# OptronV7_PCB.net
KiCad netlist of a schematic drawn in EAGLE
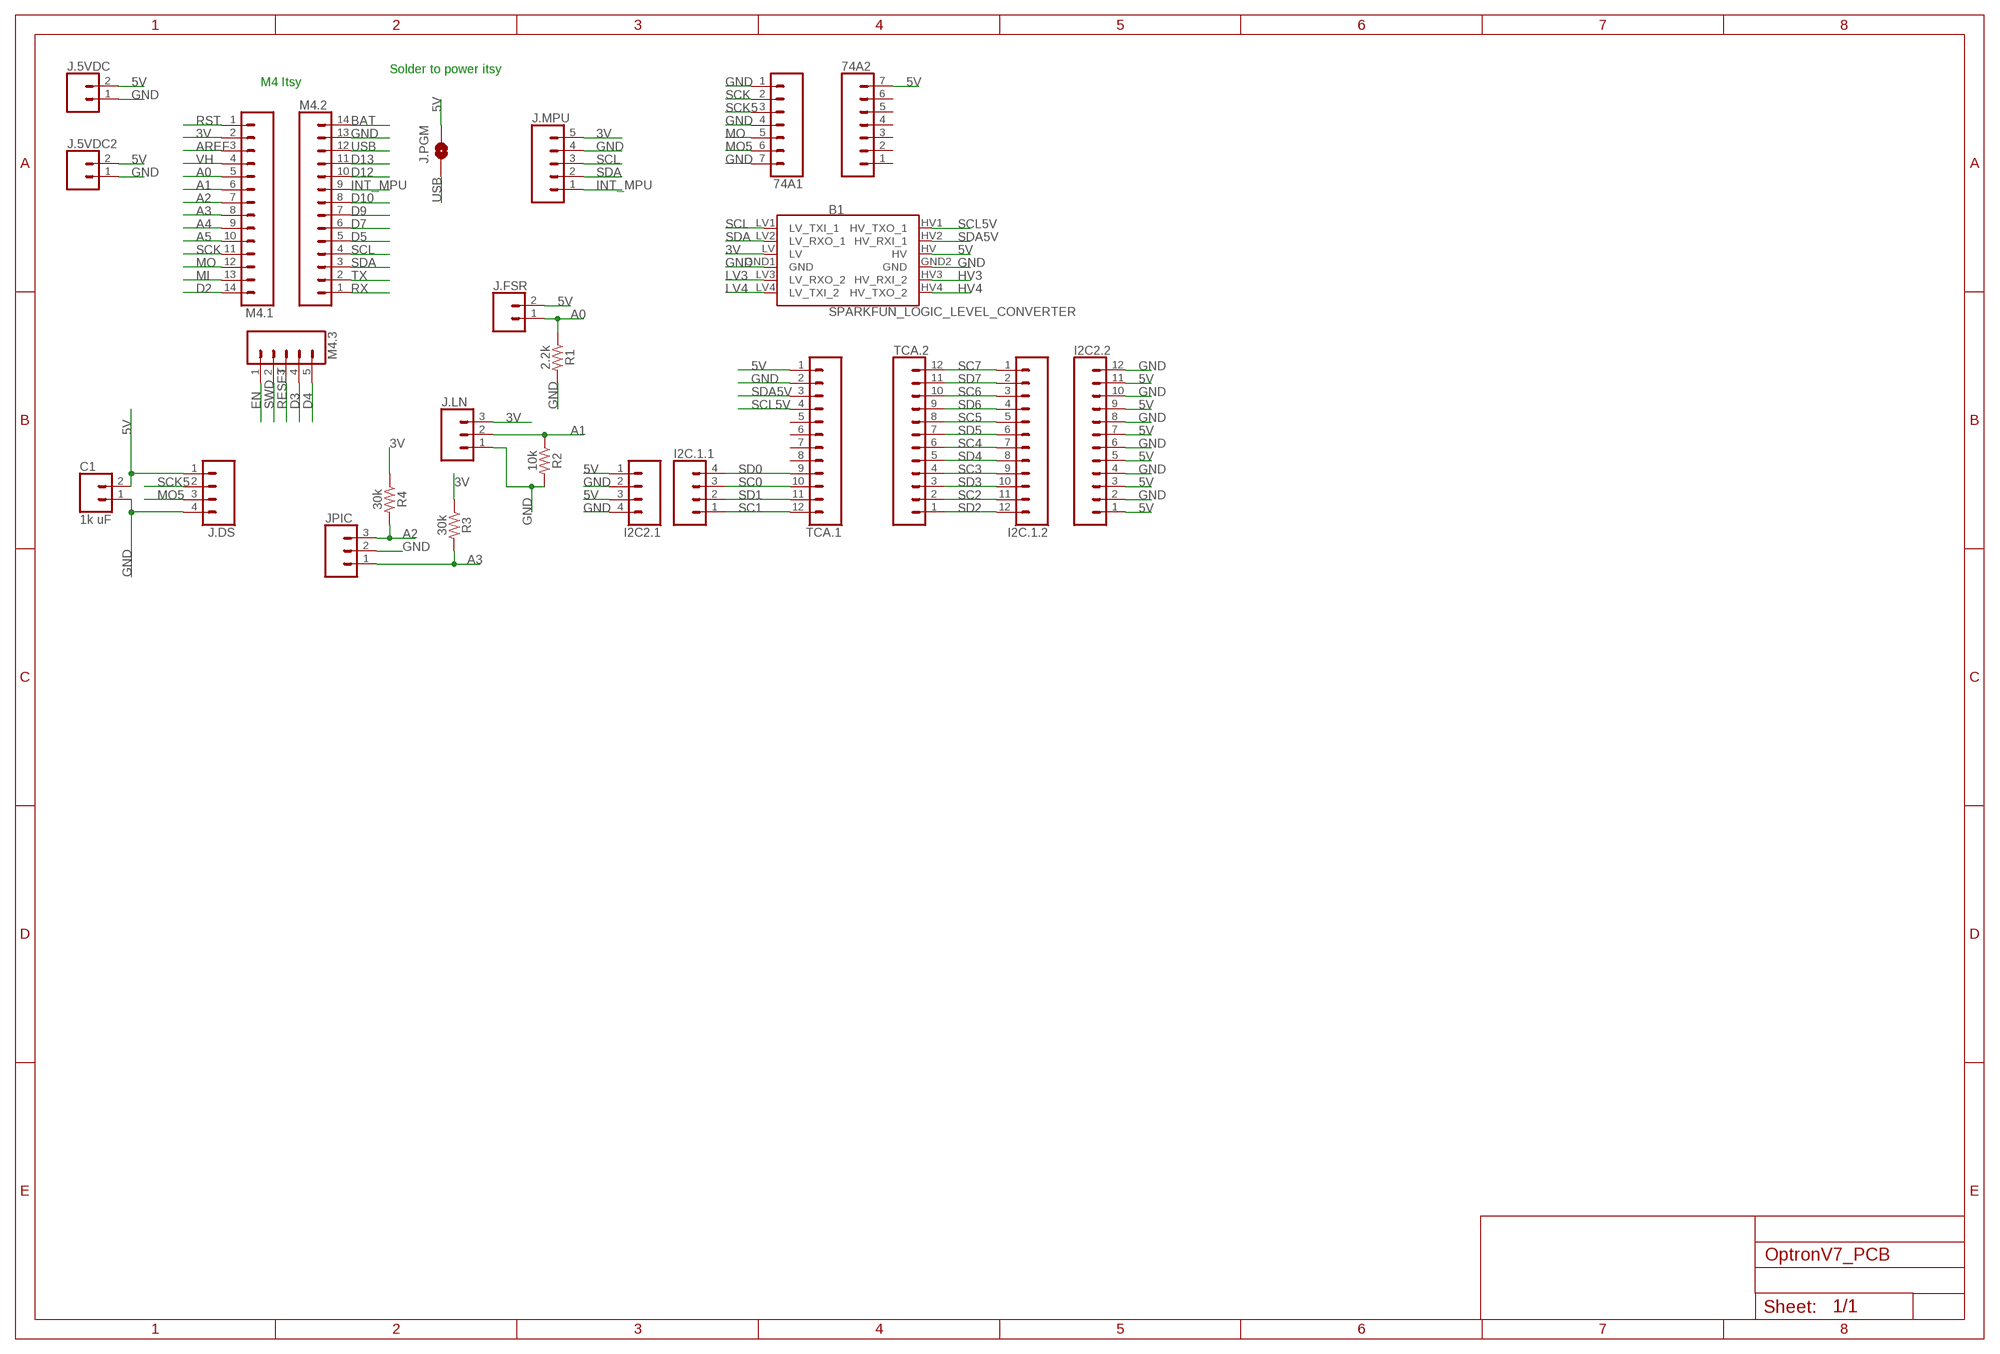
[diagram p0: schematic, sheet 1]

(export (version "E")
  (design (tool "Eeschema 10.0.6"))
  (components
    (comp (ref "74A1")
      (value "CONN_07")
      (footprint "eagle-import:1X07")
      (libsource (lib "eagle-import") (part "CONN_07"))
    )
    (comp (ref "74A2")
      (value "CONN_07")
      (footprint "eagle-import:1X07")
      (libsource (lib "eagle-import") (part "CONN_07"))
    )
    (comp (ref "B1")
      (value "SPARKFUN_LOGIC_LEVEL_CONVERTER")
      (footprint "eagle-import:SPARKFUN_LOGIC_LEVEL_CONVERTER")
      (libsource (lib "eagle-import") (part "SPARKFUN_LOGIC_LEVEL_CONVERTER"))
    )
    (comp (ref "C1")
      (value "1k uF")
      (footprint "eagle-import:1X02")
      (libsource (lib "eagle-import") (part "CONN_02"))
    )
    (comp (ref "I2C.1.1")
      (value "CONN_04")
      (footprint "eagle-import:1X04")
      (libsource (lib "eagle-import") (part "CONN_04"))
    )
    (comp (ref "I2C.1.2")
      (value "CONN_12")
      (footprint "eagle-import:1X12")
      (libsource (lib "eagle-import") (part "CONN_12"))
    )
    (comp (ref "I2C2.1")
      (value "CONN_04")
      (footprint "eagle-import:1X04")
      (libsource (lib "eagle-import") (part "CONN_04"))
    )
    (comp (ref "I2C2.2")
      (value "CONN_12")
      (footprint "eagle-import:1X12")
      (libsource (lib "eagle-import") (part "CONN_12"))
    )
    (comp (ref "J.5VDC")
      (value "CONN_02")
      (footprint "eagle-import:1X02")
      (libsource (lib "eagle-import") (part "CONN_02"))
    )
    (comp (ref "J.5VDC2")
      (value "CONN_02")
      (footprint "eagle-import:1X02")
      (libsource (lib "eagle-import") (part "CONN_02"))
    )
    (comp (ref "J.DS")
      (value "CONN_04")
      (footprint "eagle-import:1X04")
      (libsource (lib "eagle-import") (part "CONN_04"))
    )
    (comp (ref "J.FSR")
      (value "CONN_02")
      (footprint "eagle-import:1X02")
      (libsource (lib "eagle-import") (part "CONN_02"))
    )
    (comp (ref "J.LN")
      (value "CONN_03")
      (footprint "eagle-import:1X03")
      (libsource (lib "eagle-import") (part "CONN_03"))
    )
    (comp (ref "J.MPU")
      (value "CONN_05")
      (footprint "eagle-import:1X05")
      (libsource (lib "eagle-import") (part "CONN_05"))
    )
    (comp (ref "J.PGM")
      (value "JUMPER-SMT_2_NO_NO-SILK")
      (footprint "eagle-import:SMT-JUMPER_2_NO_NO-SILK")
      (libsource (lib "eagle-import") (part "JUMPER-SMT_2_NO_NO-SILK"))
    )
    (comp (ref "JPIC")
      (value "CONN_03")
      (footprint "eagle-import:1X03")
      (libsource (lib "eagle-import") (part "CONN_03"))
    )
    (comp (ref "M4.1")
      (value "CONN_14")
      (footprint "eagle-import:1X14")
      (libsource (lib "eagle-import") (part "CONN_14"))
    )
    (comp (ref "M4.2")
      (value "CONN_14")
      (footprint "eagle-import:1X14")
      (libsource (lib "eagle-import") (part "CONN_14"))
    )
    (comp (ref "M4.3")
      (value "CONN_05")
      (footprint "eagle-import:1X05")
      (libsource (lib "eagle-import") (part "CONN_05"))
    )
    (comp (ref "R1")
      (value "2.2k")
      (footprint "eagle-import:AXIAL-0.3")
      (libsource (lib "eagle-import") (part "10KOHM-HORIZ-1/4W-5%"))
    )
    (comp (ref "R2")
      (value "10k")
      (footprint "eagle-import:AXIAL-0.3")
      (libsource (lib "eagle-import") (part "10KOHM-HORIZ-1/4W-5%"))
    )
    (comp (ref "R3")
      (value "30k")
      (footprint "eagle-import:AXIAL-0.3")
      (libsource (lib "eagle-import") (part "10KOHM-HORIZ-1/4W-5%"))
    )
    (comp (ref "R4")
      (value "30k")
      (footprint "eagle-import:AXIAL-0.3")
      (libsource (lib "eagle-import") (part "10KOHM-HORIZ-1/4W-5%"))
    )
    (comp (ref "TCA.1")
      (value "CONN_12")
      (footprint "eagle-import:1X12")
      (libsource (lib "eagle-import") (part "CONN_12"))
    )
    (comp (ref "TCA.2")
      (value "CONN_12")
      (footprint "eagle-import:1X12")
      (libsource (lib "eagle-import") (part "CONN_12"))
    )
  )
  (nets
    (net (code "1") (name "/3V") (class "Default")
      (node (ref "B1") (pin "LV") (pinfunction "LV_LV") (pintype "power_in"))
      (node (ref "J.LN") (pin "3") (pinfunction "3_3") (pintype "passive"))
      (node (ref "J.MPU") (pin "5") (pinfunction "5_5") (pintype "passive"))
      (node (ref "M4.1") (pin "2") (pinfunction "2_2") (pintype "passive"))
      (node (ref "R3") (pin "P$1") (pinfunction "1_P$1") (pintype "passive"))
      (node (ref "R4") (pin "P$1") (pinfunction "1_P$1") (pintype "passive"))
    )
    (net (code "2") (name "/5V") (class "Default")
      (node (ref "74A2") (pin "7") (pinfunction "7_7") (pintype "passive"))
      (node (ref "B1") (pin "HV") (pinfunction "HV_HV") (pintype "power_in"))
      (node (ref "C1") (pin "2") (pinfunction "2_2") (pintype "passive"))
      (node (ref "I2C2.1") (pin "1") (pinfunction "1_1") (pintype "passive"))
      (node (ref "I2C2.1") (pin "3") (pinfunction "3_3") (pintype "passive"))
      (node (ref "I2C2.2") (pin "1") (pinfunction "1_1") (pintype "passive"))
      (node (ref "I2C2.2") (pin "11") (pinfunction "11_11") (pintype "passive"))
      (node (ref "I2C2.2") (pin "3") (pinfunction "3_3") (pintype "passive"))
      (node (ref "I2C2.2") (pin "5") (pinfunction "5_5") (pintype "passive"))
      (node (ref "I2C2.2") (pin "7") (pinfunction "7_7") (pintype "passive"))
      (node (ref "I2C2.2") (pin "9") (pinfunction "9_9") (pintype "passive"))
      (node (ref "J.5VDC") (pin "2") (pinfunction "2_2") (pintype "passive"))
      (node (ref "J.5VDC2") (pin "2") (pinfunction "2_2") (pintype "passive"))
      (node (ref "J.DS") (pin "1") (pinfunction "1_1") (pintype "passive"))
      (node (ref "J.FSR") (pin "2") (pinfunction "2_2") (pintype "passive"))
      (node (ref "J.PGM") (pin "2") (pinfunction "2_2") (pintype "passive"))
      (node (ref "TCA.1") (pin "1") (pinfunction "1_1") (pintype "passive"))
    )
    (net (code "3") (name "/A0") (class "Default")
      (node (ref "J.FSR") (pin "1") (pinfunction "1_1") (pintype "passive"))
      (node (ref "M4.1") (pin "5") (pinfunction "5_5") (pintype "passive"))
      (node (ref "R1") (pin "P$1") (pinfunction "1_P$1") (pintype "passive"))
    )
    (net (code "4") (name "/A1") (class "Default")
      (node (ref "J.LN") (pin "2") (pinfunction "2_2") (pintype "passive"))
      (node (ref "M4.1") (pin "6") (pinfunction "6_6") (pintype "passive"))
      (node (ref "R2") (pin "P$1") (pinfunction "1_P$1") (pintype "passive"))
    )
    (net (code "5") (name "/A2") (class "Default")
      (node (ref "JPIC") (pin "3") (pinfunction "3_3") (pintype "passive"))
      (node (ref "M4.1") (pin "7") (pinfunction "7_7") (pintype "passive"))
      (node (ref "R4") (pin "P$2") (pinfunction "2_P$2") (pintype "passive"))
    )
    (net (code "6") (name "/A3") (class "Default")
      (node (ref "JPIC") (pin "1") (pinfunction "1_1") (pintype "passive"))
      (node (ref "M4.1") (pin "8") (pinfunction "8_8") (pintype "passive"))
      (node (ref "R3") (pin "P$2") (pinfunction "2_P$2") (pintype "passive"))
    )
    (net (code "7") (name "/A4") (class "Default")
      (node (ref "M4.1") (pin "9") (pinfunction "9_9") (pintype "passive"))
    )
    (net (code "8") (name "/A5") (class "Default")
      (node (ref "M4.1") (pin "10") (pinfunction "10_10") (pintype "passive"))
    )
    (net (code "9") (name "/AREF") (class "Default")
      (node (ref "M4.1") (pin "3") (pinfunction "3_3") (pintype "passive"))
    )
    (net (code "10") (name "/BAT") (class "Default")
      (node (ref "M4.2") (pin "14") (pinfunction "14_14") (pintype "passive"))
    )
    (net (code "11") (name "/D2") (class "Default")
      (node (ref "M4.1") (pin "14") (pinfunction "14_14") (pintype "passive"))
    )
    (net (code "12") (name "/D3") (class "Default")
      (node (ref "M4.3") (pin "4") (pinfunction "4_4") (pintype "passive"))
    )
    (net (code "13") (name "/D4") (class "Default")
      (node (ref "M4.3") (pin "5") (pinfunction "5_5") (pintype "passive"))
    )
    (net (code "14") (name "/D5") (class "Default")
      (node (ref "M4.2") (pin "5") (pinfunction "5_5") (pintype "passive"))
    )
    (net (code "15") (name "/D7") (class "Default")
      (node (ref "M4.2") (pin "6") (pinfunction "6_6") (pintype "passive"))
    )
    (net (code "16") (name "/D9") (class "Default")
      (node (ref "M4.2") (pin "7") (pinfunction "7_7") (pintype "passive"))
    )
    (net (code "17") (name "/D10") (class "Default")
      (node (ref "M4.2") (pin "8") (pinfunction "8_8") (pintype "passive"))
    )
    (net (code "18") (name "/D12") (class "Default")
      (node (ref "M4.2") (pin "10") (pinfunction "10_10") (pintype "passive"))
    )
    (net (code "19") (name "/D13") (class "Default")
      (node (ref "M4.2") (pin "11") (pinfunction "11_11") (pintype "passive"))
    )
    (net (code "20") (name "/EN") (class "Default")
      (node (ref "M4.3") (pin "1") (pinfunction "1_1") (pintype "passive"))
    )
    (net (code "21") (name "/GND") (class "Default")
      (node (ref "74A1") (pin "1") (pinfunction "1_1") (pintype "passive"))
      (node (ref "74A1") (pin "4") (pinfunction "4_4") (pintype "passive"))
      (node (ref "74A1") (pin "7") (pinfunction "7_7") (pintype "passive"))
      (node (ref "B1") (pin "GND1") (pinfunction "GND_GND1") (pintype "power_in"))
      (node (ref "B1") (pin "GND2") (pinfunction "GND_GND2") (pintype "power_in"))
      (node (ref "C1") (pin "1") (pinfunction "1_1") (pintype "passive"))
      (node (ref "I2C2.1") (pin "2") (pinfunction "2_2") (pintype "passive"))
      (node (ref "I2C2.1") (pin "4") (pinfunction "4_4") (pintype "passive"))
      (node (ref "I2C2.2") (pin "10") (pinfunction "10_10") (pintype "passive"))
      (node (ref "I2C2.2") (pin "12") (pinfunction "12_12") (pintype "passive"))
      (node (ref "I2C2.2") (pin "2") (pinfunction "2_2") (pintype "passive"))
      (node (ref "I2C2.2") (pin "4") (pinfunction "4_4") (pintype "passive"))
      (node (ref "I2C2.2") (pin "6") (pinfunction "6_6") (pintype "passive"))
      (node (ref "I2C2.2") (pin "8") (pinfunction "8_8") (pintype "passive"))
      (node (ref "J.5VDC") (pin "1") (pinfunction "1_1") (pintype "passive"))
      (node (ref "J.5VDC2") (pin "1") (pinfunction "1_1") (pintype "passive"))
      (node (ref "J.DS") (pin "4") (pinfunction "4_4") (pintype "passive"))
      (node (ref "J.LN") (pin "1") (pinfunction "1_1") (pintype "passive"))
      (node (ref "J.MPU") (pin "4") (pinfunction "4_4") (pintype "passive"))
      (node (ref "JPIC") (pin "2") (pinfunction "2_2") (pintype "passive"))
      (node (ref "M4.2") (pin "13") (pinfunction "13_13") (pintype "passive"))
      (node (ref "R1") (pin "P$2") (pinfunction "2_P$2") (pintype "passive"))
      (node (ref "R2") (pin "P$2") (pinfunction "2_P$2") (pintype "passive"))
      (node (ref "TCA.1") (pin "2") (pinfunction "2_2") (pintype "passive"))
    )
    (net (code "22") (name "/HV3") (class "Default")
      (node (ref "B1") (pin "HV3") (pinfunction "HV_RXI_2_HV3") (pintype "bidirectional"))
    )
    (net (code "23") (name "/HV4") (class "Default")
      (node (ref "B1") (pin "HV4") (pinfunction "HV_TXO_2_HV4") (pintype "bidirectional"))
    )
    (net (code "24") (name "/INT_MPU") (class "Default")
      (node (ref "J.MPU") (pin "1") (pinfunction "1_1") (pintype "passive"))
      (node (ref "M4.2") (pin "9") (pinfunction "9_9") (pintype "passive"))
    )
    (net (code "25") (name "/LV3") (class "Default")
      (node (ref "B1") (pin "LV3") (pinfunction "LV_RXO_2_LV3") (pintype "bidirectional"))
    )
    (net (code "26") (name "/LV4") (class "Default")
      (node (ref "B1") (pin "LV4") (pinfunction "LV_TXI_2_LV4") (pintype "bidirectional"))
    )
    (net (code "27") (name "/MI") (class "Default")
      (node (ref "M4.1") (pin "13") (pinfunction "13_13") (pintype "passive"))
    )
    (net (code "28") (name "/MO") (class "Default")
      (node (ref "74A1") (pin "5") (pinfunction "5_5") (pintype "passive"))
      (node (ref "M4.1") (pin "12") (pinfunction "12_12") (pintype "passive"))
    )
    (net (code "29") (name "/MO5") (class "Default")
      (node (ref "74A1") (pin "6") (pinfunction "6_6") (pintype "passive"))
      (node (ref "J.DS") (pin "3") (pinfunction "3_3") (pintype "passive"))
    )
    (net (code "30") (name "/RESET") (class "Default")
      (node (ref "M4.3") (pin "3") (pinfunction "3_3") (pintype "passive"))
    )
    (net (code "31") (name "/RST") (class "Default")
      (node (ref "M4.1") (pin "1") (pinfunction "1_1") (pintype "passive"))
    )
    (net (code "32") (name "/RX") (class "Default")
      (node (ref "M4.2") (pin "1") (pinfunction "1_1") (pintype "passive"))
    )
    (net (code "33") (name "/SC0") (class "Default")
      (node (ref "I2C.1.1") (pin "3") (pinfunction "3_3") (pintype "passive"))
      (node (ref "TCA.1") (pin "10") (pinfunction "10_10") (pintype "passive"))
    )
    (net (code "34") (name "/SC1") (class "Default")
      (node (ref "I2C.1.1") (pin "1") (pinfunction "1_1") (pintype "passive"))
      (node (ref "TCA.1") (pin "12") (pinfunction "12_12") (pintype "passive"))
    )
    (net (code "35") (name "/SC2") (class "Default")
      (node (ref "I2C.1.2") (pin "11") (pinfunction "11_11") (pintype "passive"))
      (node (ref "TCA.2") (pin "2") (pinfunction "2_2") (pintype "passive"))
    )
    (net (code "36") (name "/SC3") (class "Default")
      (node (ref "I2C.1.2") (pin "9") (pinfunction "9_9") (pintype "passive"))
      (node (ref "TCA.2") (pin "4") (pinfunction "4_4") (pintype "passive"))
    )
    (net (code "37") (name "/SC4") (class "Default")
      (node (ref "I2C.1.2") (pin "7") (pinfunction "7_7") (pintype "passive"))
      (node (ref "TCA.2") (pin "6") (pinfunction "6_6") (pintype "passive"))
    )
    (net (code "38") (name "/SC5") (class "Default")
      (node (ref "I2C.1.2") (pin "5") (pinfunction "5_5") (pintype "passive"))
      (node (ref "TCA.2") (pin "8") (pinfunction "8_8") (pintype "passive"))
    )
    (net (code "39") (name "/SC6") (class "Default")
      (node (ref "I2C.1.2") (pin "3") (pinfunction "3_3") (pintype "passive"))
      (node (ref "TCA.2") (pin "10") (pinfunction "10_10") (pintype "passive"))
    )
    (net (code "40") (name "/SC7") (class "Default")
      (node (ref "I2C.1.2") (pin "1") (pinfunction "1_1") (pintype "passive"))
      (node (ref "TCA.2") (pin "12") (pinfunction "12_12") (pintype "passive"))
    )
    (net (code "41") (name "/SCK") (class "Default")
      (node (ref "74A1") (pin "2") (pinfunction "2_2") (pintype "passive"))
      (node (ref "M4.1") (pin "11") (pinfunction "11_11") (pintype "passive"))
    )
    (net (code "42") (name "/SCK5") (class "Default")
      (node (ref "74A1") (pin "3") (pinfunction "3_3") (pintype "passive"))
      (node (ref "J.DS") (pin "2") (pinfunction "2_2") (pintype "passive"))
    )
    (net (code "43") (name "/SCL") (class "Default")
      (node (ref "B1") (pin "LV1") (pinfunction "LV_TXI_1_LV1") (pintype "bidirectional"))
      (node (ref "J.MPU") (pin "3") (pinfunction "3_3") (pintype "passive"))
      (node (ref "M4.2") (pin "4") (pinfunction "4_4") (pintype "passive"))
    )
    (net (code "44") (name "/SCL5V") (class "Default")
      (node (ref "B1") (pin "HV1") (pinfunction "HV_TXO_1_HV1") (pintype "bidirectional"))
      (node (ref "TCA.1") (pin "4") (pinfunction "4_4") (pintype "passive"))
    )
    (net (code "45") (name "/SD0") (class "Default")
      (node (ref "I2C.1.1") (pin "4") (pinfunction "4_4") (pintype "passive"))
      (node (ref "TCA.1") (pin "9") (pinfunction "9_9") (pintype "passive"))
    )
    (net (code "46") (name "/SD1") (class "Default")
      (node (ref "I2C.1.1") (pin "2") (pinfunction "2_2") (pintype "passive"))
      (node (ref "TCA.1") (pin "11") (pinfunction "11_11") (pintype "passive"))
    )
    (net (code "47") (name "/SD2") (class "Default")
      (node (ref "I2C.1.2") (pin "12") (pinfunction "12_12") (pintype "passive"))
      (node (ref "TCA.2") (pin "1") (pinfunction "1_1") (pintype "passive"))
    )
    (net (code "48") (name "/SD3") (class "Default")
      (node (ref "I2C.1.2") (pin "10") (pinfunction "10_10") (pintype "passive"))
      (node (ref "TCA.2") (pin "3") (pinfunction "3_3") (pintype "passive"))
    )
    (net (code "49") (name "/SD4") (class "Default")
      (node (ref "I2C.1.2") (pin "8") (pinfunction "8_8") (pintype "passive"))
      (node (ref "TCA.2") (pin "5") (pinfunction "5_5") (pintype "passive"))
    )
    (net (code "50") (name "/SD5") (class "Default")
      (node (ref "I2C.1.2") (pin "6") (pinfunction "6_6") (pintype "passive"))
      (node (ref "TCA.2") (pin "7") (pinfunction "7_7") (pintype "passive"))
    )
    (net (code "51") (name "/SD6") (class "Default")
      (node (ref "I2C.1.2") (pin "4") (pinfunction "4_4") (pintype "passive"))
      (node (ref "TCA.2") (pin "9") (pinfunction "9_9") (pintype "passive"))
    )
    (net (code "52") (name "/SD7") (class "Default")
      (node (ref "I2C.1.2") (pin "2") (pinfunction "2_2") (pintype "passive"))
      (node (ref "TCA.2") (pin "11") (pinfunction "11_11") (pintype "passive"))
    )
    (net (code "53") (name "/SDA") (class "Default")
      (node (ref "B1") (pin "LV2") (pinfunction "LV_RXO_1_LV2") (pintype "bidirectional"))
      (node (ref "J.MPU") (pin "2") (pinfunction "2_2") (pintype "passive"))
      (node (ref "M4.2") (pin "3") (pinfunction "3_3") (pintype "passive"))
    )
    (net (code "54") (name "/SDA5V") (class "Default")
      (node (ref "B1") (pin "HV2") (pinfunction "HV_RXI_1_HV2") (pintype "bidirectional"))
      (node (ref "TCA.1") (pin "3") (pinfunction "3_3") (pintype "passive"))
    )
    (net (code "55") (name "/SWD") (class "Default")
      (node (ref "M4.3") (pin "2") (pinfunction "2_2") (pintype "passive"))
    )
    (net (code "56") (name "/TX") (class "Default")
      (node (ref "M4.2") (pin "2") (pinfunction "2_2") (pintype "passive"))
    )
    (net (code "57") (name "/USB") (class "Default")
      (node (ref "J.PGM") (pin "1") (pinfunction "1_1") (pintype "passive"))
      (node (ref "M4.2") (pin "12") (pinfunction "12_12") (pintype "passive"))
    )
    (net (code "58") (name "/VH") (class "Default")
      (node (ref "M4.1") (pin "4") (pinfunction "4_4") (pintype "passive"))
    )
    (net (code "59") (name "unconnected-(74A2-Pad1)") (class "Default")
      (node (ref "74A2") (pin "1") (pinfunction "1_1") (pintype "passive"))
    )
    (net (code "60") (name "unconnected-(74A2-Pad2)") (class "Default")
      (node (ref "74A2") (pin "2") (pinfunction "2_2") (pintype "passive"))
    )
    (net (code "61") (name "unconnected-(74A2-Pad3)") (class "Default")
      (node (ref "74A2") (pin "3") (pinfunction "3_3") (pintype "passive"))
    )
    (net (code "62") (name "unconnected-(74A2-Pad4)") (class "Default")
      (node (ref "74A2") (pin "4") (pinfunction "4_4") (pintype "passive"))
    )
    (net (code "63") (name "unconnected-(74A2-Pad5)") (class "Default")
      (node (ref "74A2") (pin "5") (pinfunction "5_5") (pintype "passive"))
    )
    (net (code "64") (name "unconnected-(74A2-Pad6)") (class "Default")
      (node (ref "74A2") (pin "6") (pinfunction "6_6") (pintype "passive"))
    )
    (net (code "65") (name "unconnected-(TCA.1-Pad5)") (class "Default")
      (node (ref "TCA.1") (pin "5") (pinfunction "5_5") (pintype "passive"))
    )
    (net (code "66") (name "unconnected-(TCA.1-Pad6)") (class "Default")
      (node (ref "TCA.1") (pin "6") (pinfunction "6_6") (pintype "passive"))
    )
    (net (code "67") (name "unconnected-(TCA.1-Pad7)") (class "Default")
      (node (ref "TCA.1") (pin "7") (pinfunction "7_7") (pintype "passive"))
    )
    (net (code "68") (name "unconnected-(TCA.1-Pad8)") (class "Default")
      (node (ref "TCA.1") (pin "8") (pinfunction "8_8") (pintype "passive"))
    )
  )
)
